# 5v_AC-DC_REGULATOR.net
KiCad netlist of a schematic drawn in EAGLE
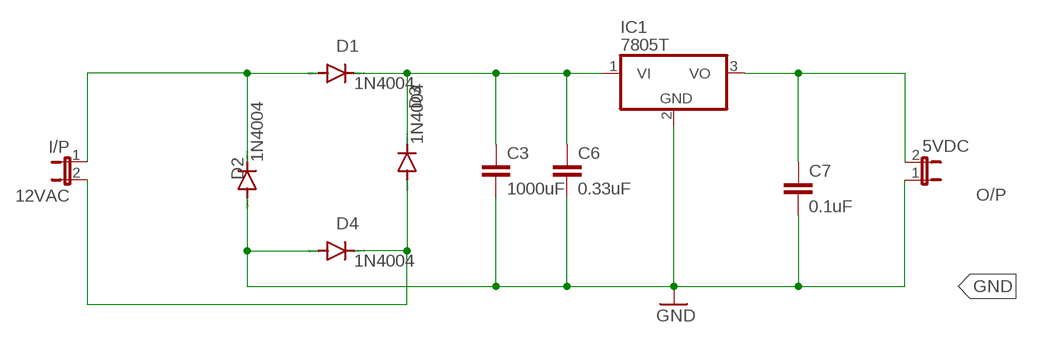
[diagram p0: schematic, sheet 1]

(export (version "E")
  (design (tool "Eeschema 10.0.6"))
  (components
    (comp (ref "C3")
      (value "1000uF")
      (footprint "eagle-import:C2.5-3")
      (libsource (lib "eagle-import") (part "C2,5-3"))
    )
    (comp (ref "C6")
      (value "0.33uF")
      (footprint "eagle-import:C2.5-3")
      (libsource (lib "eagle-import") (part "C2,5-3"))
    )
    (comp (ref "C7")
      (value "0.1uF")
      (footprint "eagle-import:C2.5-3")
      (libsource (lib "eagle-import") (part "C2,5-3"))
    )
    (comp (ref "D1")
      (value "1N4004")
      (footprint "eagle-import:DO41-10")
      (libsource (lib "eagle-import") (part "1N4004"))
    )
    (comp (ref "D2")
      (value "1N4004")
      (footprint "eagle-import:DO41-10")
      (libsource (lib "eagle-import") (part "1N4004"))
    )
    (comp (ref "D3")
      (value "1N4004")
      (footprint "eagle-import:DO41-10")
      (libsource (lib "eagle-import") (part "1N4004"))
    )
    (comp (ref "D4")
      (value "1N4004")
      (footprint "eagle-import:DO41-10")
      (libsource (lib "eagle-import") (part "1N4004"))
    )
    (comp (ref "I/P")
      (value "12VAC")
      (footprint "eagle-import:JP1")
      (libsource (lib "eagle-import") (part "JP1E"))
    )
    (comp (ref "IC1")
      (value "7805T")
      (footprint "eagle-import:TO220H")
      (libsource (lib "eagle-import") (part "78T05"))
    )
    (comp (ref "O/P")
      (value "5VDC")
      (footprint "eagle-import:JP1")
      (libsource (lib "eagle-import") (part "JP1E"))
    )
  )
  (nets
    (net (code "1") (name "GND") (class "Default")
      (node (ref "C3") (pin "2") (pinfunction "2_2") (pintype "passive"))
      (node (ref "C6") (pin "2") (pinfunction "2_2") (pintype "passive"))
      (node (ref "C7") (pin "2") (pinfunction "2_2") (pintype "passive"))
      (node (ref "D2") (pin "A") (pinfunction "A_A") (pintype "passive"))
      (node (ref "D4") (pin "A") (pinfunction "A_A") (pintype "passive"))
      (node (ref "IC1") (pin "2") (pinfunction "GND_2") (pintype "passive"))
      (node (ref "O/P") (pin "1") (pinfunction "1_1") (pintype "passive"))
    )
    (net (code "2") (name "Net-(D1-PadA)") (class "Default")
      (node (ref "D1") (pin "A") (pinfunction "A_A") (pintype "passive"))
      (node (ref "D2") (pin "C") (pinfunction "C_C") (pintype "passive"))
      (node (ref "I/P") (pin "1") (pinfunction "1_1") (pintype "passive"))
    )
    (net (code "3") (name "Net-(D3-PadA)") (class "Default")
      (node (ref "D3") (pin "A") (pinfunction "A_A") (pintype "passive"))
      (node (ref "D4") (pin "C") (pinfunction "C_C") (pintype "passive"))
      (node (ref "I/P") (pin "2") (pinfunction "2_2") (pintype "passive"))
    )
    (net (code "4") (name "Net-(IC1-VI)") (class "Default")
      (node (ref "C3") (pin "1") (pinfunction "1_1") (pintype "passive"))
      (node (ref "C6") (pin "1") (pinfunction "1_1") (pintype "passive"))
      (node (ref "D1") (pin "C") (pinfunction "C_C") (pintype "passive"))
      (node (ref "D3") (pin "C") (pinfunction "C_C") (pintype "passive"))
      (node (ref "IC1") (pin "1") (pinfunction "VI_1") (pintype "input"))
    )
    (net (code "5") (name "Net-(IC1-VO)") (class "Default")
      (node (ref "C7") (pin "1") (pinfunction "1_1") (pintype "passive"))
      (node (ref "IC1") (pin "3") (pinfunction "VO_3") (pintype "passive"))
      (node (ref "O/P") (pin "2") (pinfunction "2_2") (pintype "passive"))
    )
  )
)
